# Robomow_PCG5002E_schematic.net
KiCad netlist of a schematic drawn in EAGLE
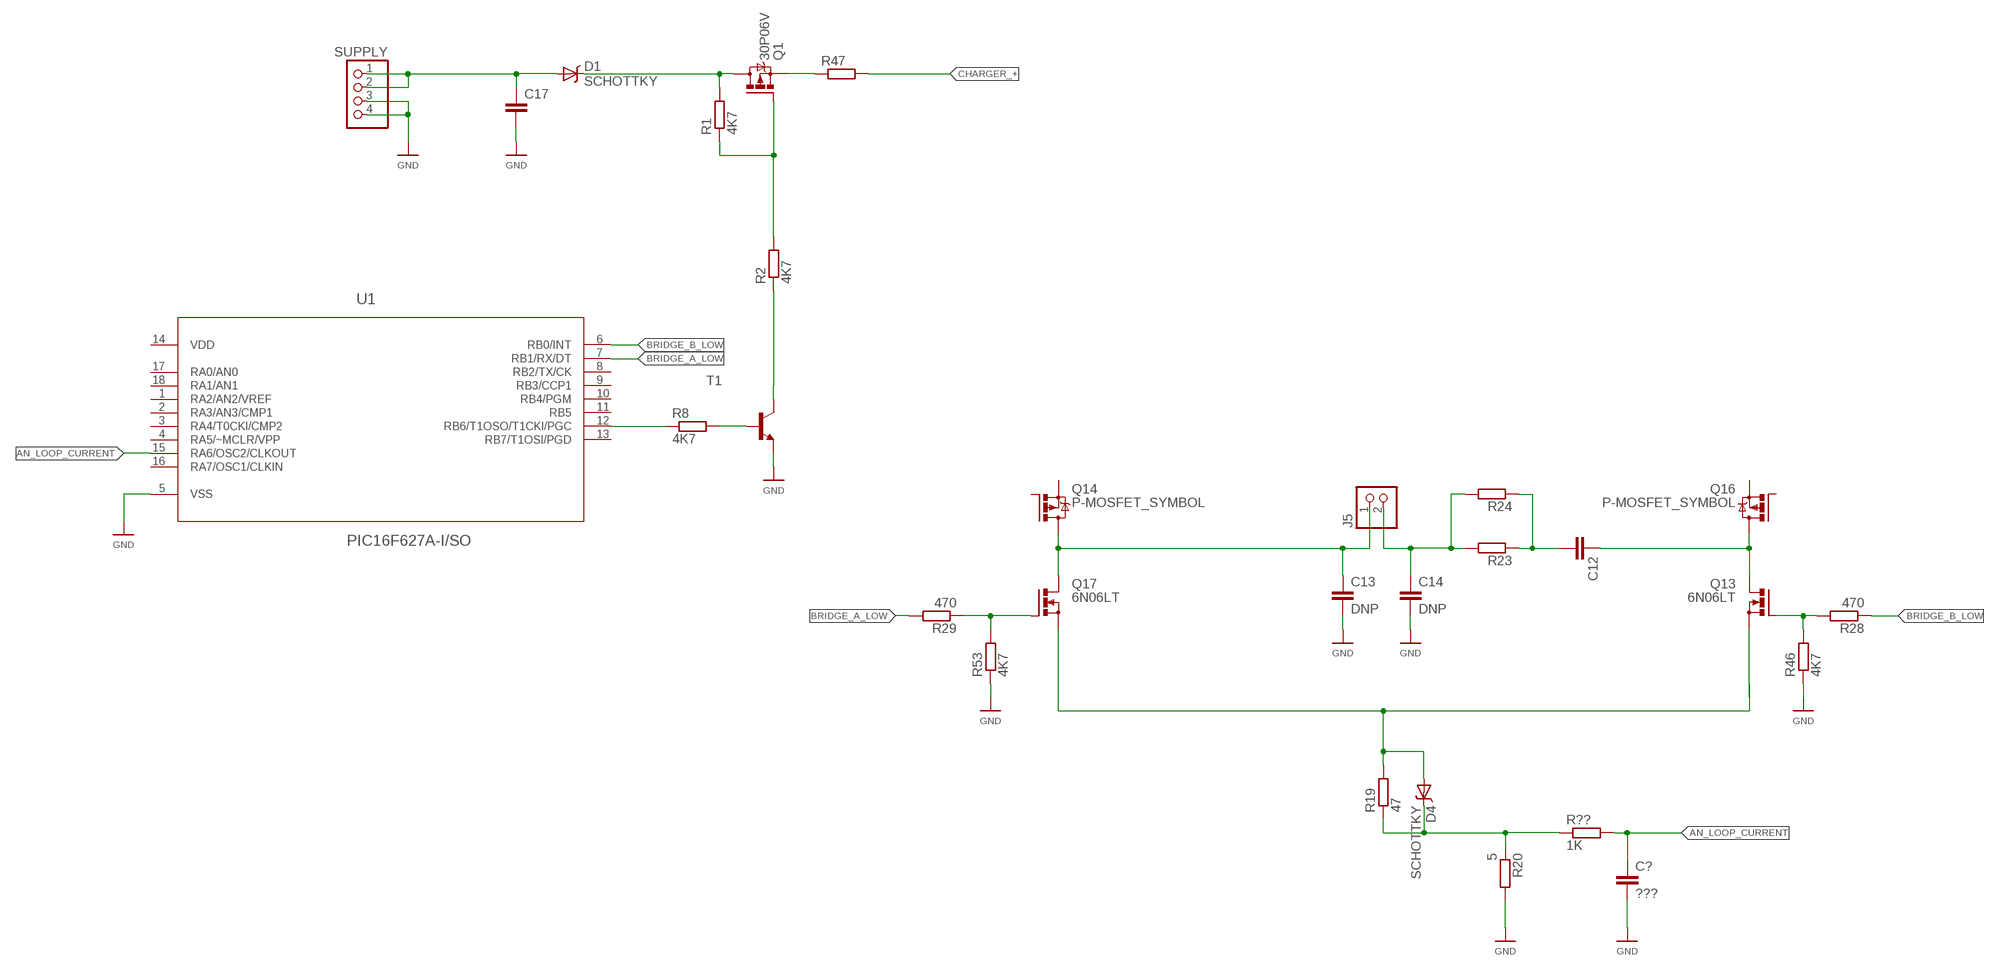
[diagram p0: schematic, sheet 1]

(export (version "E")
  (design (tool "Eeschema 10.0.6"))
  (components
    (comp (ref "C12")
      (value "C-EU050-030X075")
      (footprint "eagle-import:C050-030X075")
      (libsource (lib "eagle-import") (part "C-EU050-030X075"))
    )
    (comp (ref "C13")
      (value "DNP")
      (footprint "eagle-import:C0603")
      (libsource (lib "eagle-import") (part "C-EUC0603"))
    )
    (comp (ref "C14")
      (value "DNP")
      (footprint "eagle-import:C0603")
      (libsource (lib "eagle-import") (part "C-EUC0603"))
    )
    (comp (ref "C17")
      (value "C-EU050-030X075")
      (footprint "eagle-import:C050-030X075")
      (libsource (lib "eagle-import") (part "C-EU050-030X075"))
    )
    (comp (ref "C?")
      (value "???")
      (footprint "eagle-import:C0603")
      (libsource (lib "eagle-import") (part "C-EUC0603"))
    )
    (comp (ref "D1")
      (value "SCHOTTKY")
      (footprint "eagle-import:DO-214AC")
      (libsource (lib "eagle-import") (part "SCHOTTKY"))
    )
    (comp (ref "D4")
      (value "SCHOTTKY")
      (footprint "eagle-import:DO-214AC")
      (libsource (lib "eagle-import") (part "SCHOTTKY"))
    )
    (comp (ref "J5")
      (value "PINHD-1X2")
      (footprint "eagle-import:1X02")
      (libsource (lib "eagle-import") (part "PINHD-1X2"))
    )
    (comp (ref "R1")
      (value "4K7")
      (footprint "eagle-import:R0603")
      (libsource (lib "eagle-import") (part "R-EU_R0603"))
    )
    (comp (ref "R2")
      (value "4K7")
      (footprint "eagle-import:R0603")
      (libsource (lib "eagle-import") (part "R-EU_R0603"))
    )
    (comp (ref "R8")
      (value "4K7")
      (footprint "eagle-import:R0603")
      (libsource (lib "eagle-import") (part "R-EU_R0603"))
    )
    (comp (ref "R19")
      (value "47")
      (footprint "eagle-import:R0603")
      (libsource (lib "eagle-import") (part "R-EU_R0603"))
    )
    (comp (ref "R20")
      (value "5")
      (footprint "eagle-import:R0603")
      (libsource (lib "eagle-import") (part "R-EU_R0603"))
    )
    (comp (ref "R23")
      (value "R-EU_0414/15")
      (footprint "eagle-import:0414_15")
      (libsource (lib "eagle-import") (part "R-EU_0414/15"))
    )
    (comp (ref "R24")
      (value "R-EU_0414/15")
      (footprint "eagle-import:0414_15")
      (libsource (lib "eagle-import") (part "R-EU_0414/15"))
    )
    (comp (ref "R28")
      (value "470")
      (footprint "eagle-import:R0603")
      (libsource (lib "eagle-import") (part "R-EU_R0603"))
    )
    (comp (ref "R29")
      (value "470")
      (footprint "eagle-import:R0603")
      (libsource (lib "eagle-import") (part "R-EU_R0603"))
    )
    (comp (ref "R46")
      (value "4K7")
      (footprint "eagle-import:R0603")
      (libsource (lib "eagle-import") (part "R-EU_R0603"))
    )
    (comp (ref "R47")
      (value "R-EU_0414/15")
      (footprint "eagle-import:0414_15")
      (libsource (lib "eagle-import") (part "R-EU_0414/15"))
    )
    (comp (ref "R53")
      (value "4K7")
      (footprint "eagle-import:R0603")
      (libsource (lib "eagle-import") (part "R-EU_R0603"))
    )
    (comp (ref "R??")
      (value "1K")
      (footprint "eagle-import:R0603")
      (libsource (lib "eagle-import") (part "R-EU_R0603"))
    )
    (comp (ref "SUPPLY")
      (value "PINHD-1X4")
      (footprint "eagle-import:1X04")
      (libsource (lib "eagle-import") (part "PINHD-1X4"))
    )
    (comp (ref "T1")
      (value "-NPN-SOT23-EBC")
      (footprint "eagle-import:SOT23-EBC")
      (libsource (lib "eagle-import") (part "-NPN-SOT23-EBC"))
    )
    (comp (ref "U1")
      (value "PIC16F627A-I/SO")
      (footprint "eagle-import:SOIC127P1030X265-18N")
      (libsource (lib "eagle-import") (part "PIC16F627A-I/SO"))
    )
  )
  (nets
    (net (code "1") (name "/VDD") (class "Default")
      (node (ref "U1") (pin "14") (pinfunction "VDD_14") (pintype "power_in"))
    )
    (net (code "2") (name "AN_LOOP_CURRENT") (class "Default")
      (node (ref "C?") (pin "1") (pinfunction "1_1") (pintype "passive"))
      (node (ref "R??") (pin "2") (pinfunction "2_2") (pintype "passive"))
      (node (ref "U1") (pin "15") (pinfunction "RA6/OSC2/CLKOUT_15") (pintype "bidirectional"))
    )
    (net (code "3") (name "BRIDGE_A_LOW") (class "Default")
      (node (ref "R29") (pin "2") (pinfunction "2_2") (pintype "passive"))
      (node (ref "U1") (pin "7") (pinfunction "RB1/RX/DT_7") (pintype "bidirectional"))
    )
    (net (code "4") (name "BRIDGE_B_LOW") (class "Default")
      (node (ref "R28") (pin "1") (pinfunction "1_1") (pintype "passive"))
      (node (ref "U1") (pin "6") (pinfunction "RB0/INT_6") (pintype "bidirectional"))
    )
    (net (code "5") (name "CHARGER_+") (class "Default")
      (node (ref "R47") (pin "2") (pinfunction "2_2") (pintype "passive"))
    )
    (net (code "6") (name "GND") (class "Default")
      (node (ref "C13") (pin "2") (pinfunction "2_2") (pintype "passive"))
      (node (ref "C14") (pin "2") (pinfunction "2_2") (pintype "passive"))
      (node (ref "C17") (pin "2") (pinfunction "2_2") (pintype "passive"))
      (node (ref "C?") (pin "2") (pinfunction "2_2") (pintype "passive"))
      (node (ref "R20") (pin "2") (pinfunction "2_2") (pintype "passive"))
      (node (ref "R46") (pin "1") (pinfunction "1_1") (pintype "passive"))
      (node (ref "R53") (pin "1") (pinfunction "1_1") (pintype "passive"))
      (node (ref "SUPPLY") (pin "3") (pinfunction "3_3") (pintype "passive"))
      (node (ref "SUPPLY") (pin "4") (pinfunction "4_4") (pintype "passive"))
      (node (ref "T1") (pin "E") (pinfunction "E_E") (pintype "passive"))
      (node (ref "U1") (pin "5") (pinfunction "VSS_5") (pintype "power_in"))
    )
    (net (code "7") (name "Net-(C12-Pad2)") (class "Default")
      (node (ref "C12") (pin "2") (pinfunction "2_2") (pintype "passive"))
      (node (ref "R23") (pin "1") (pinfunction "1_1") (pintype "passive"))
      (node (ref "R24") (pin "1") (pinfunction "1_1") (pintype "passive"))
    )
    (net (code "8") (name "Net-(C13-Pad1)") (class "Default")
      (node (ref "C13") (pin "1") (pinfunction "1_1") (pintype "passive"))
      (node (ref "J5") (pin "1") (pinfunction "1_1") (pintype "passive"))
    )
    (net (code "9") (name "Net-(C14-Pad1)") (class "Default")
      (node (ref "C14") (pin "1") (pinfunction "1_1") (pintype "passive"))
      (node (ref "J5") (pin "2") (pinfunction "2_2") (pintype "passive"))
      (node (ref "R23") (pin "2") (pinfunction "2_2") (pintype "passive"))
      (node (ref "R24") (pin "2") (pinfunction "2_2") (pintype "passive"))
    )
    (net (code "10") (name "Net-(C17-Pad1)") (class "Default")
      (node (ref "C17") (pin "1") (pinfunction "1_1") (pintype "passive"))
      (node (ref "D1") (pin "A") (pinfunction "A_A") (pintype "passive"))
      (node (ref "SUPPLY") (pin "1") (pinfunction "1_1") (pintype "passive"))
      (node (ref "SUPPLY") (pin "2") (pinfunction "2_2") (pintype "passive"))
    )
    (net (code "11") (name "Net-(D1-PadC)") (class "Default")
      (node (ref "D1") (pin "C") (pinfunction "C_C") (pintype "passive"))
      (node (ref "R1") (pin "2") (pinfunction "2_2") (pintype "passive"))
    )
    (net (code "12") (name "Net-(D4-PadA)") (class "Default")
      (node (ref "D4") (pin "A") (pinfunction "A_A") (pintype "passive"))
      (node (ref "R19") (pin "2") (pinfunction "2_2") (pintype "passive"))
    )
    (net (code "13") (name "Net-(D4-PadC)") (class "Default")
      (node (ref "D4") (pin "C") (pinfunction "C_C") (pintype "passive"))
      (node (ref "R19") (pin "1") (pinfunction "1_1") (pintype "passive"))
      (node (ref "R20") (pin "1") (pinfunction "1_1") (pintype "passive"))
      (node (ref "R??") (pin "1") (pinfunction "1_1") (pintype "passive"))
    )
    (net (code "14") (name "Net-(R1-Pad1)") (class "Default")
      (node (ref "R1") (pin "1") (pinfunction "1_1") (pintype "passive"))
      (node (ref "R2") (pin "2") (pinfunction "2_2") (pintype "passive"))
    )
    (net (code "15") (name "Net-(R2-Pad1)") (class "Default")
      (node (ref "R2") (pin "1") (pinfunction "1_1") (pintype "passive"))
      (node (ref "T1") (pin "C") (pinfunction "C_C") (pintype "passive"))
    )
    (net (code "16") (name "Net-(R8-Pad2)") (class "Default")
      (node (ref "R8") (pin "2") (pinfunction "2_2") (pintype "passive"))
      (node (ref "T1") (pin "B") (pinfunction "B_B") (pintype "passive"))
    )
    (net (code "17") (name "Net-(R28-Pad2)") (class "Default")
      (node (ref "R28") (pin "2") (pinfunction "2_2") (pintype "passive"))
      (node (ref "R46") (pin "2") (pinfunction "2_2") (pintype "passive"))
    )
    (net (code "18") (name "Net-(R29-Pad1)") (class "Default")
      (node (ref "R29") (pin "1") (pinfunction "1_1") (pintype "passive"))
      (node (ref "R53") (pin "2") (pinfunction "2_2") (pintype "passive"))
    )
    (net (code "19") (name "Net-(U1-RB6{slash}T1OSO{slash}T1CKI{slash}PGC)") (class "Default")
      (node (ref "R8") (pin "1") (pinfunction "1_1") (pintype "passive"))
      (node (ref "U1") (pin "12") (pinfunction "RB6/T1OSO/T1CKI/PGC_12") (pintype "bidirectional"))
    )
    (net (code "20") (name "unconnected-(C12-Pad1)") (class "Default")
      (node (ref "C12") (pin "1") (pinfunction "1_1") (pintype "passive"))
    )
    (net (code "21") (name "unconnected-(R47-Pad1)") (class "Default")
      (node (ref "R47") (pin "1") (pinfunction "1_1") (pintype "passive"))
    )
    (net (code "22") (name "unconnected-(U1-RA0{slash}AN0-Pad17)") (class "Default")
      (node (ref "U1") (pin "17") (pinfunction "RA0/AN0_17") (pintype "bidirectional"))
    )
    (net (code "23") (name "unconnected-(U1-RA1{slash}AN1-Pad18)") (class "Default")
      (node (ref "U1") (pin "18") (pinfunction "RA1/AN1_18") (pintype "bidirectional"))
    )
    (net (code "24") (name "unconnected-(U1-RA2{slash}AN2{slash}VREF-Pad1)") (class "Default")
      (node (ref "U1") (pin "1") (pinfunction "RA2/AN2/VREF_1") (pintype "bidirectional"))
    )
    (net (code "25") (name "unconnected-(U1-RA3{slash}AN3{slash}CMP1-Pad2)") (class "Default")
      (node (ref "U1") (pin "2") (pinfunction "RA3/AN3/CMP1_2") (pintype "bidirectional"))
    )
    (net (code "26") (name "unconnected-(U1-RA4{slash}T0CKI{slash}CMP2-Pad3)") (class "Default")
      (node (ref "U1") (pin "3") (pinfunction "RA4/T0CKI/CMP2_3") (pintype "bidirectional"))
    )
    (net (code "27") (name "unconnected-(U1-RA5{slash}~{MCLR{slash}VPP}-Pad4)") (class "Default")
      (node (ref "U1") (pin "4") (pinfunction "RA5/~{MCLR/VPP}_4") (pintype "bidirectional"))
    )
    (net (code "28") (name "unconnected-(U1-RA7{slash}OSC1{slash}CLKIN-Pad16)") (class "Default")
      (node (ref "U1") (pin "16") (pinfunction "RA7/OSC1/CLKIN_16") (pintype "bidirectional"))
    )
    (net (code "29") (name "unconnected-(U1-RB2{slash}TX{slash}CK-Pad8)") (class "Default")
      (node (ref "U1") (pin "8") (pinfunction "RB2/TX/CK_8") (pintype "bidirectional"))
    )
    (net (code "30") (name "unconnected-(U1-RB3{slash}CCP1-Pad9)") (class "Default")
      (node (ref "U1") (pin "9") (pinfunction "RB3/CCP1_9") (pintype "bidirectional"))
    )
    (net (code "31") (name "unconnected-(U1-RB4{slash}PGM-Pad10)") (class "Default")
      (node (ref "U1") (pin "10") (pinfunction "RB4/PGM_10") (pintype "bidirectional"))
    )
    (net (code "32") (name "unconnected-(U1-RB5-Pad11)") (class "Default")
      (node (ref "U1") (pin "11") (pinfunction "RB5_11") (pintype "bidirectional"))
    )
    (net (code "33") (name "unconnected-(U1-RB7{slash}T1OSI{slash}PGD-Pad13)") (class "Default")
      (node (ref "U1") (pin "13") (pinfunction "RB7/T1OSI/PGD_13") (pintype "bidirectional"))
    )
  )
)
